# PCB.net
KiCad netlist of a schematic drawn in EasyEDA Pro
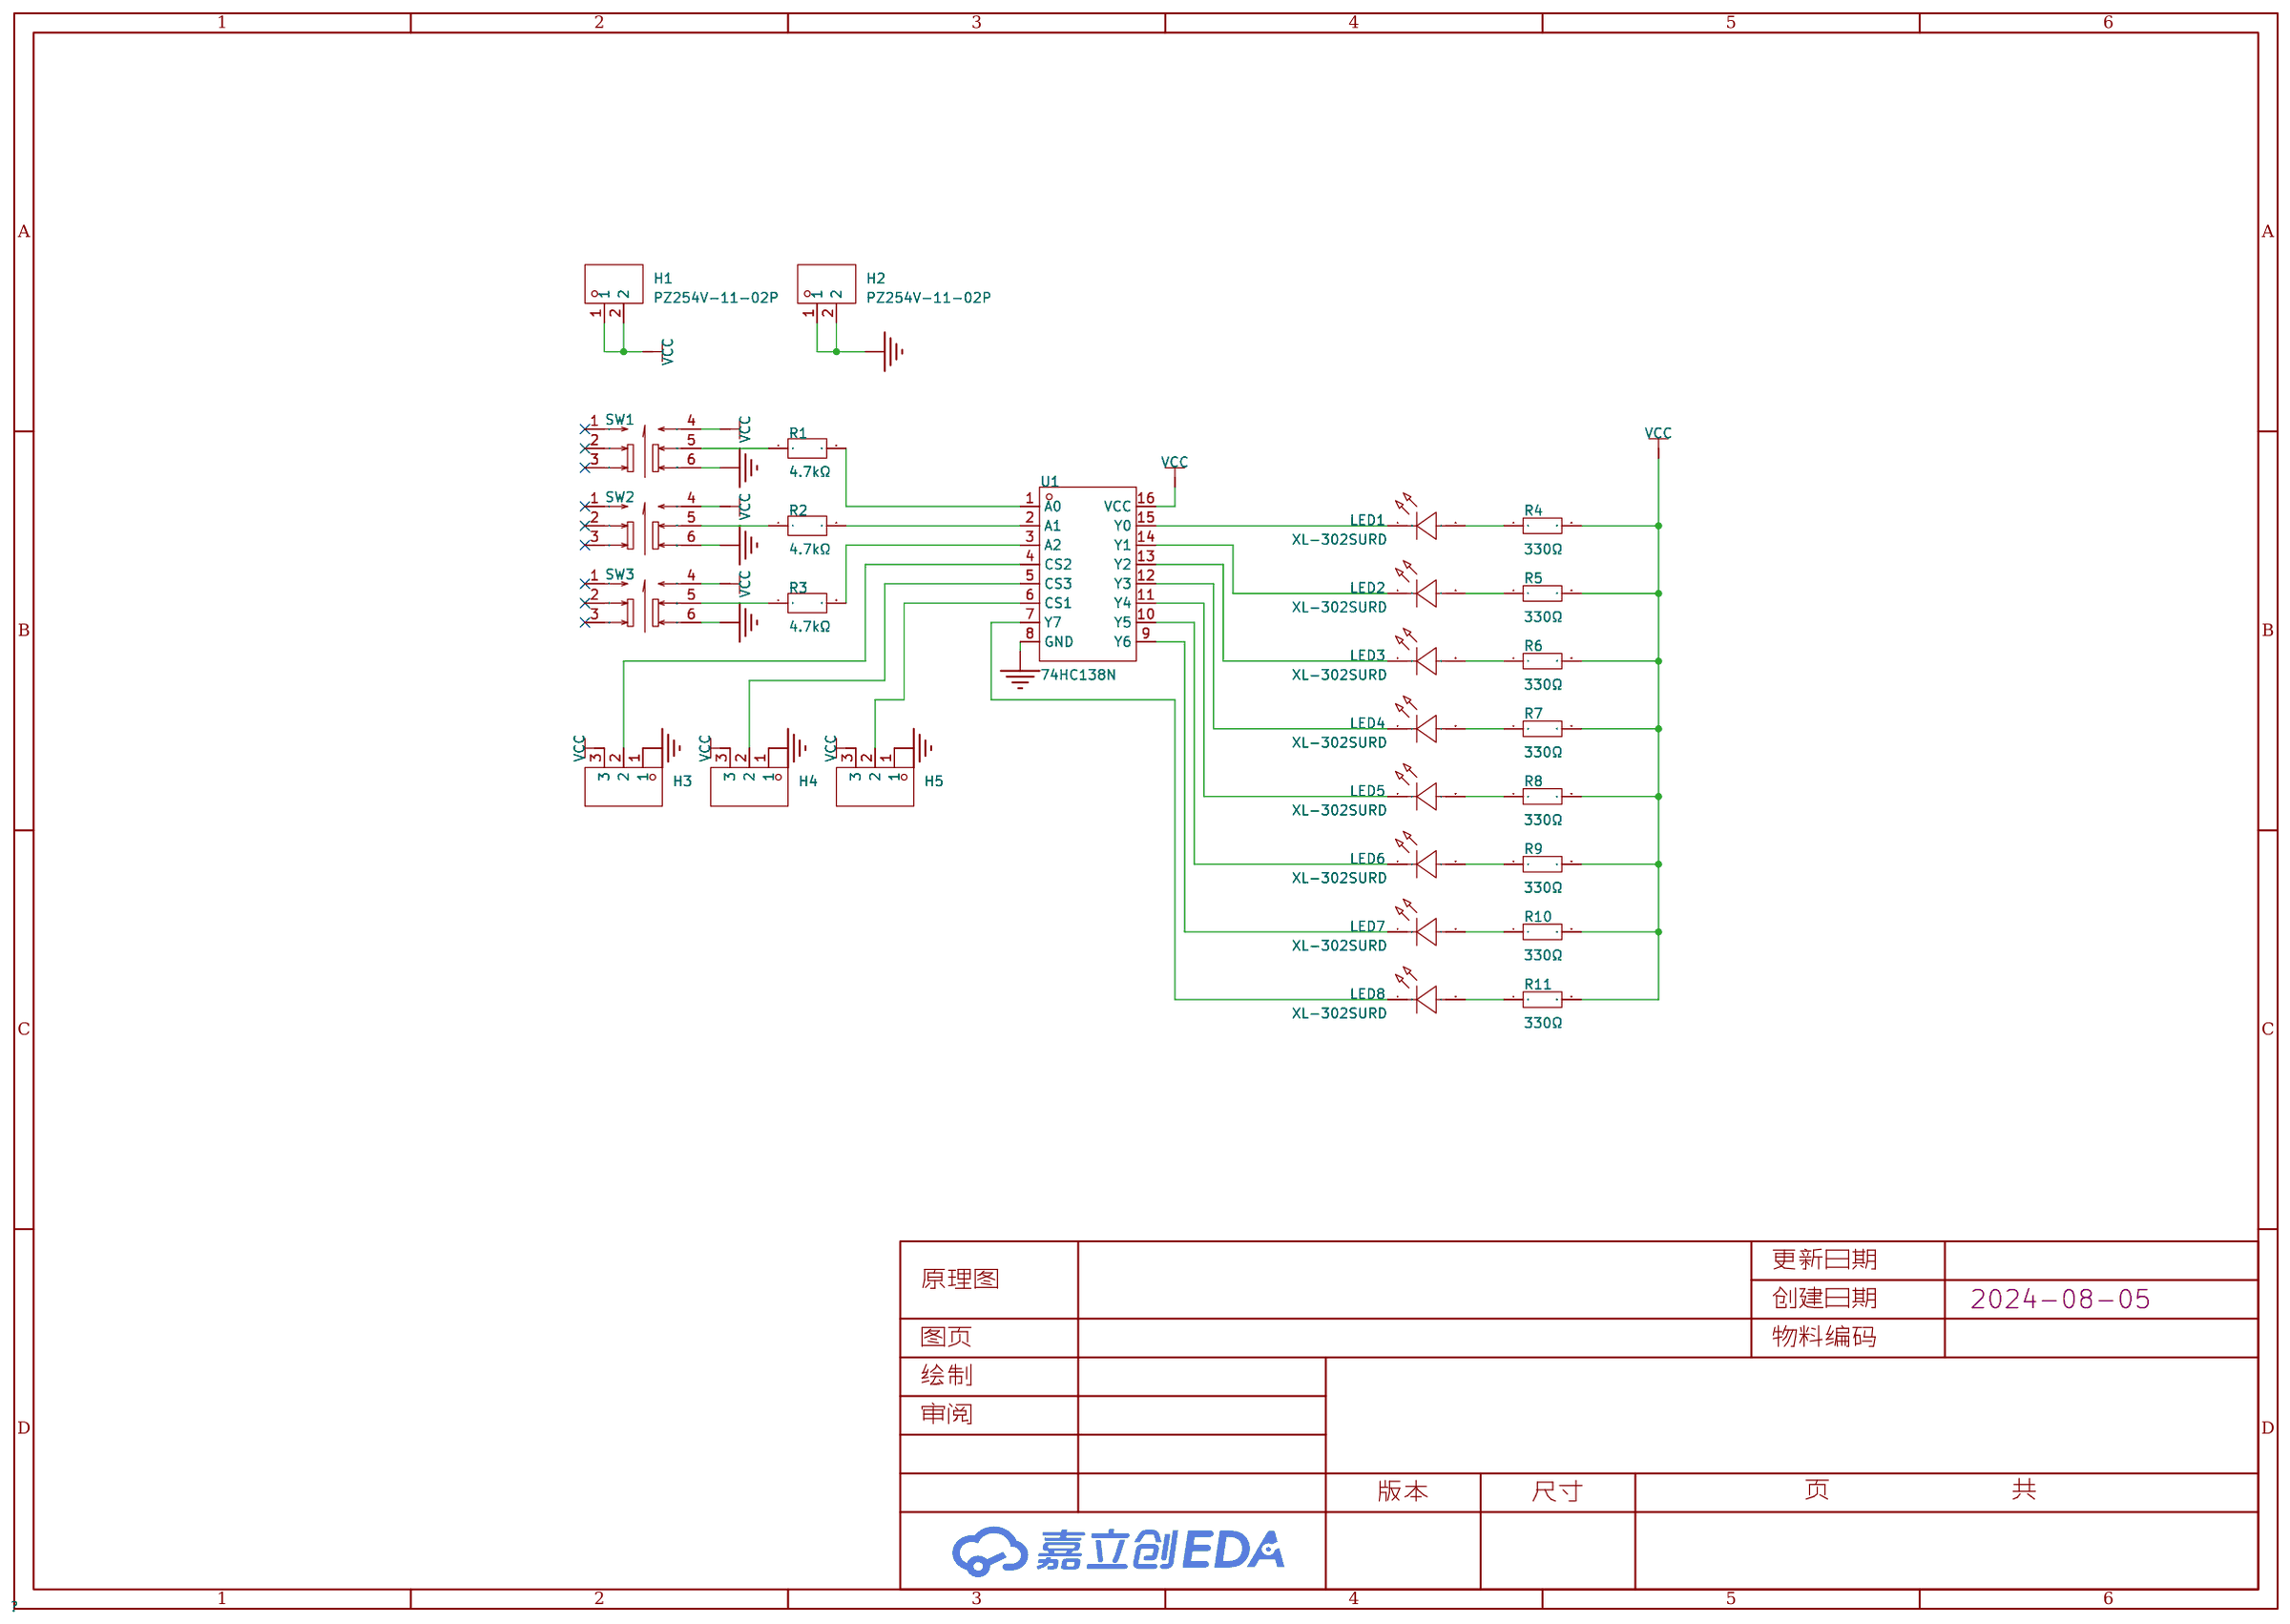
[diagram p0: 38译码电路]
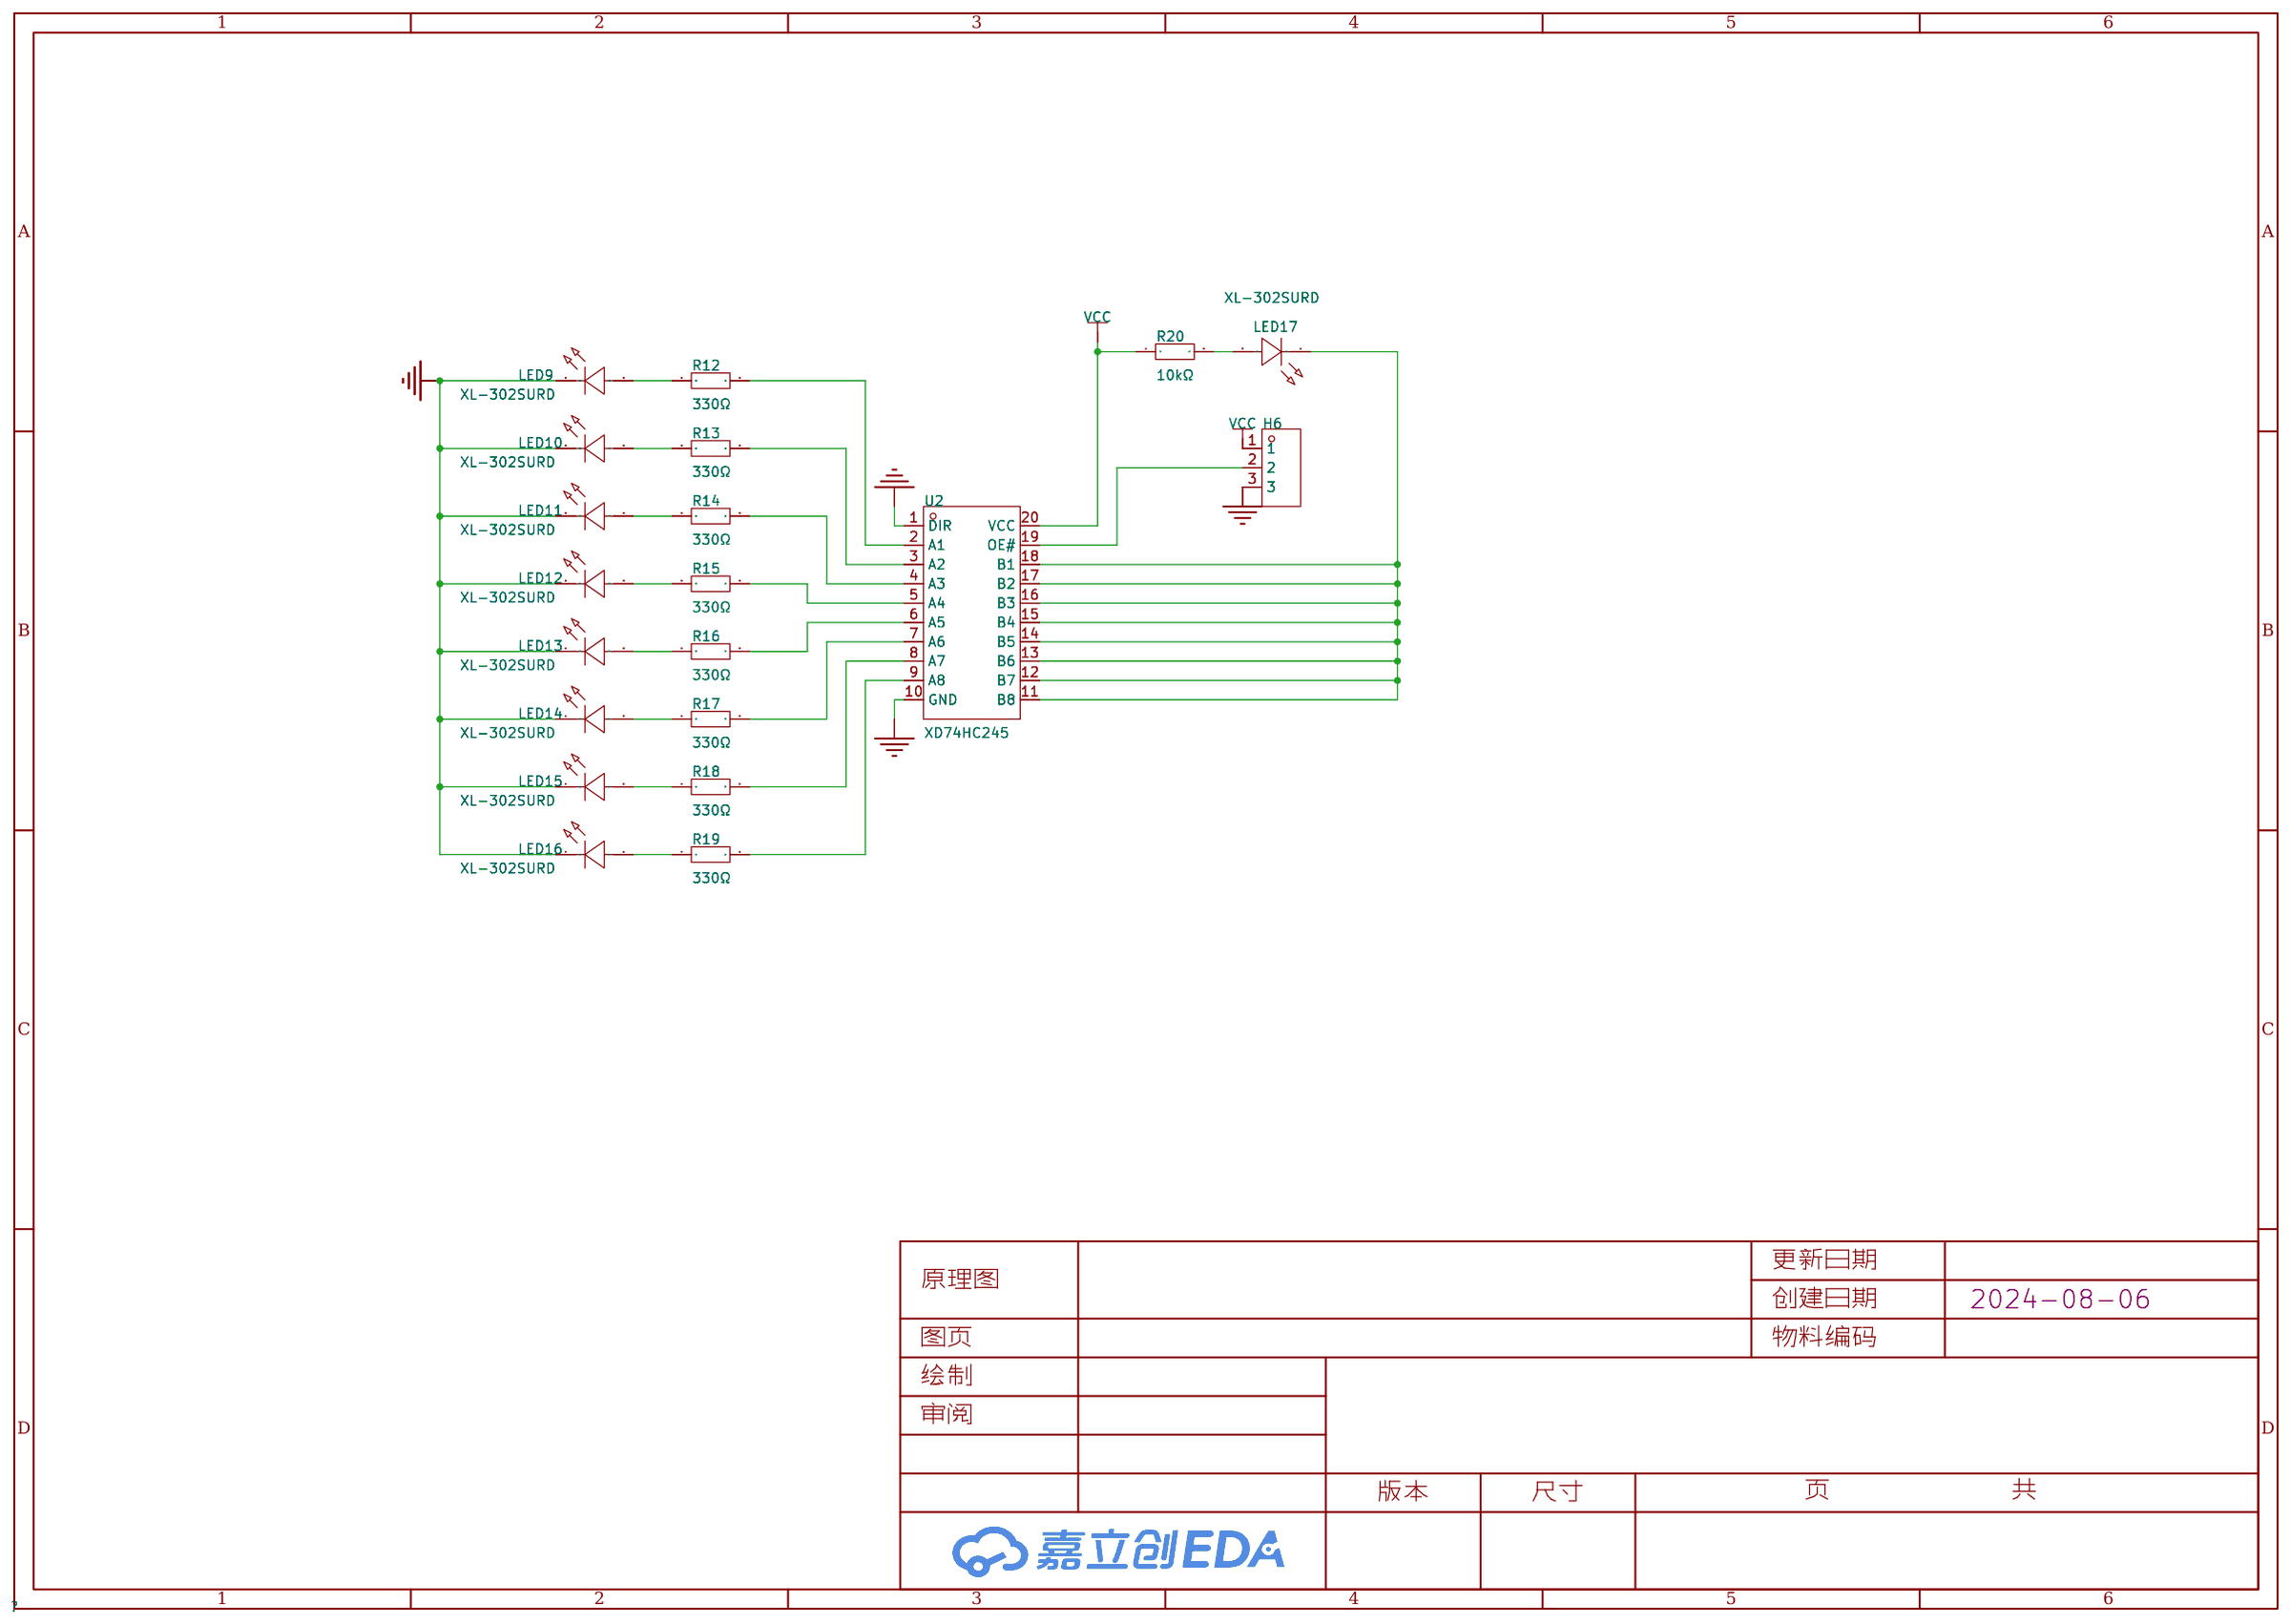
[diagram p1: 245信号放大电路]
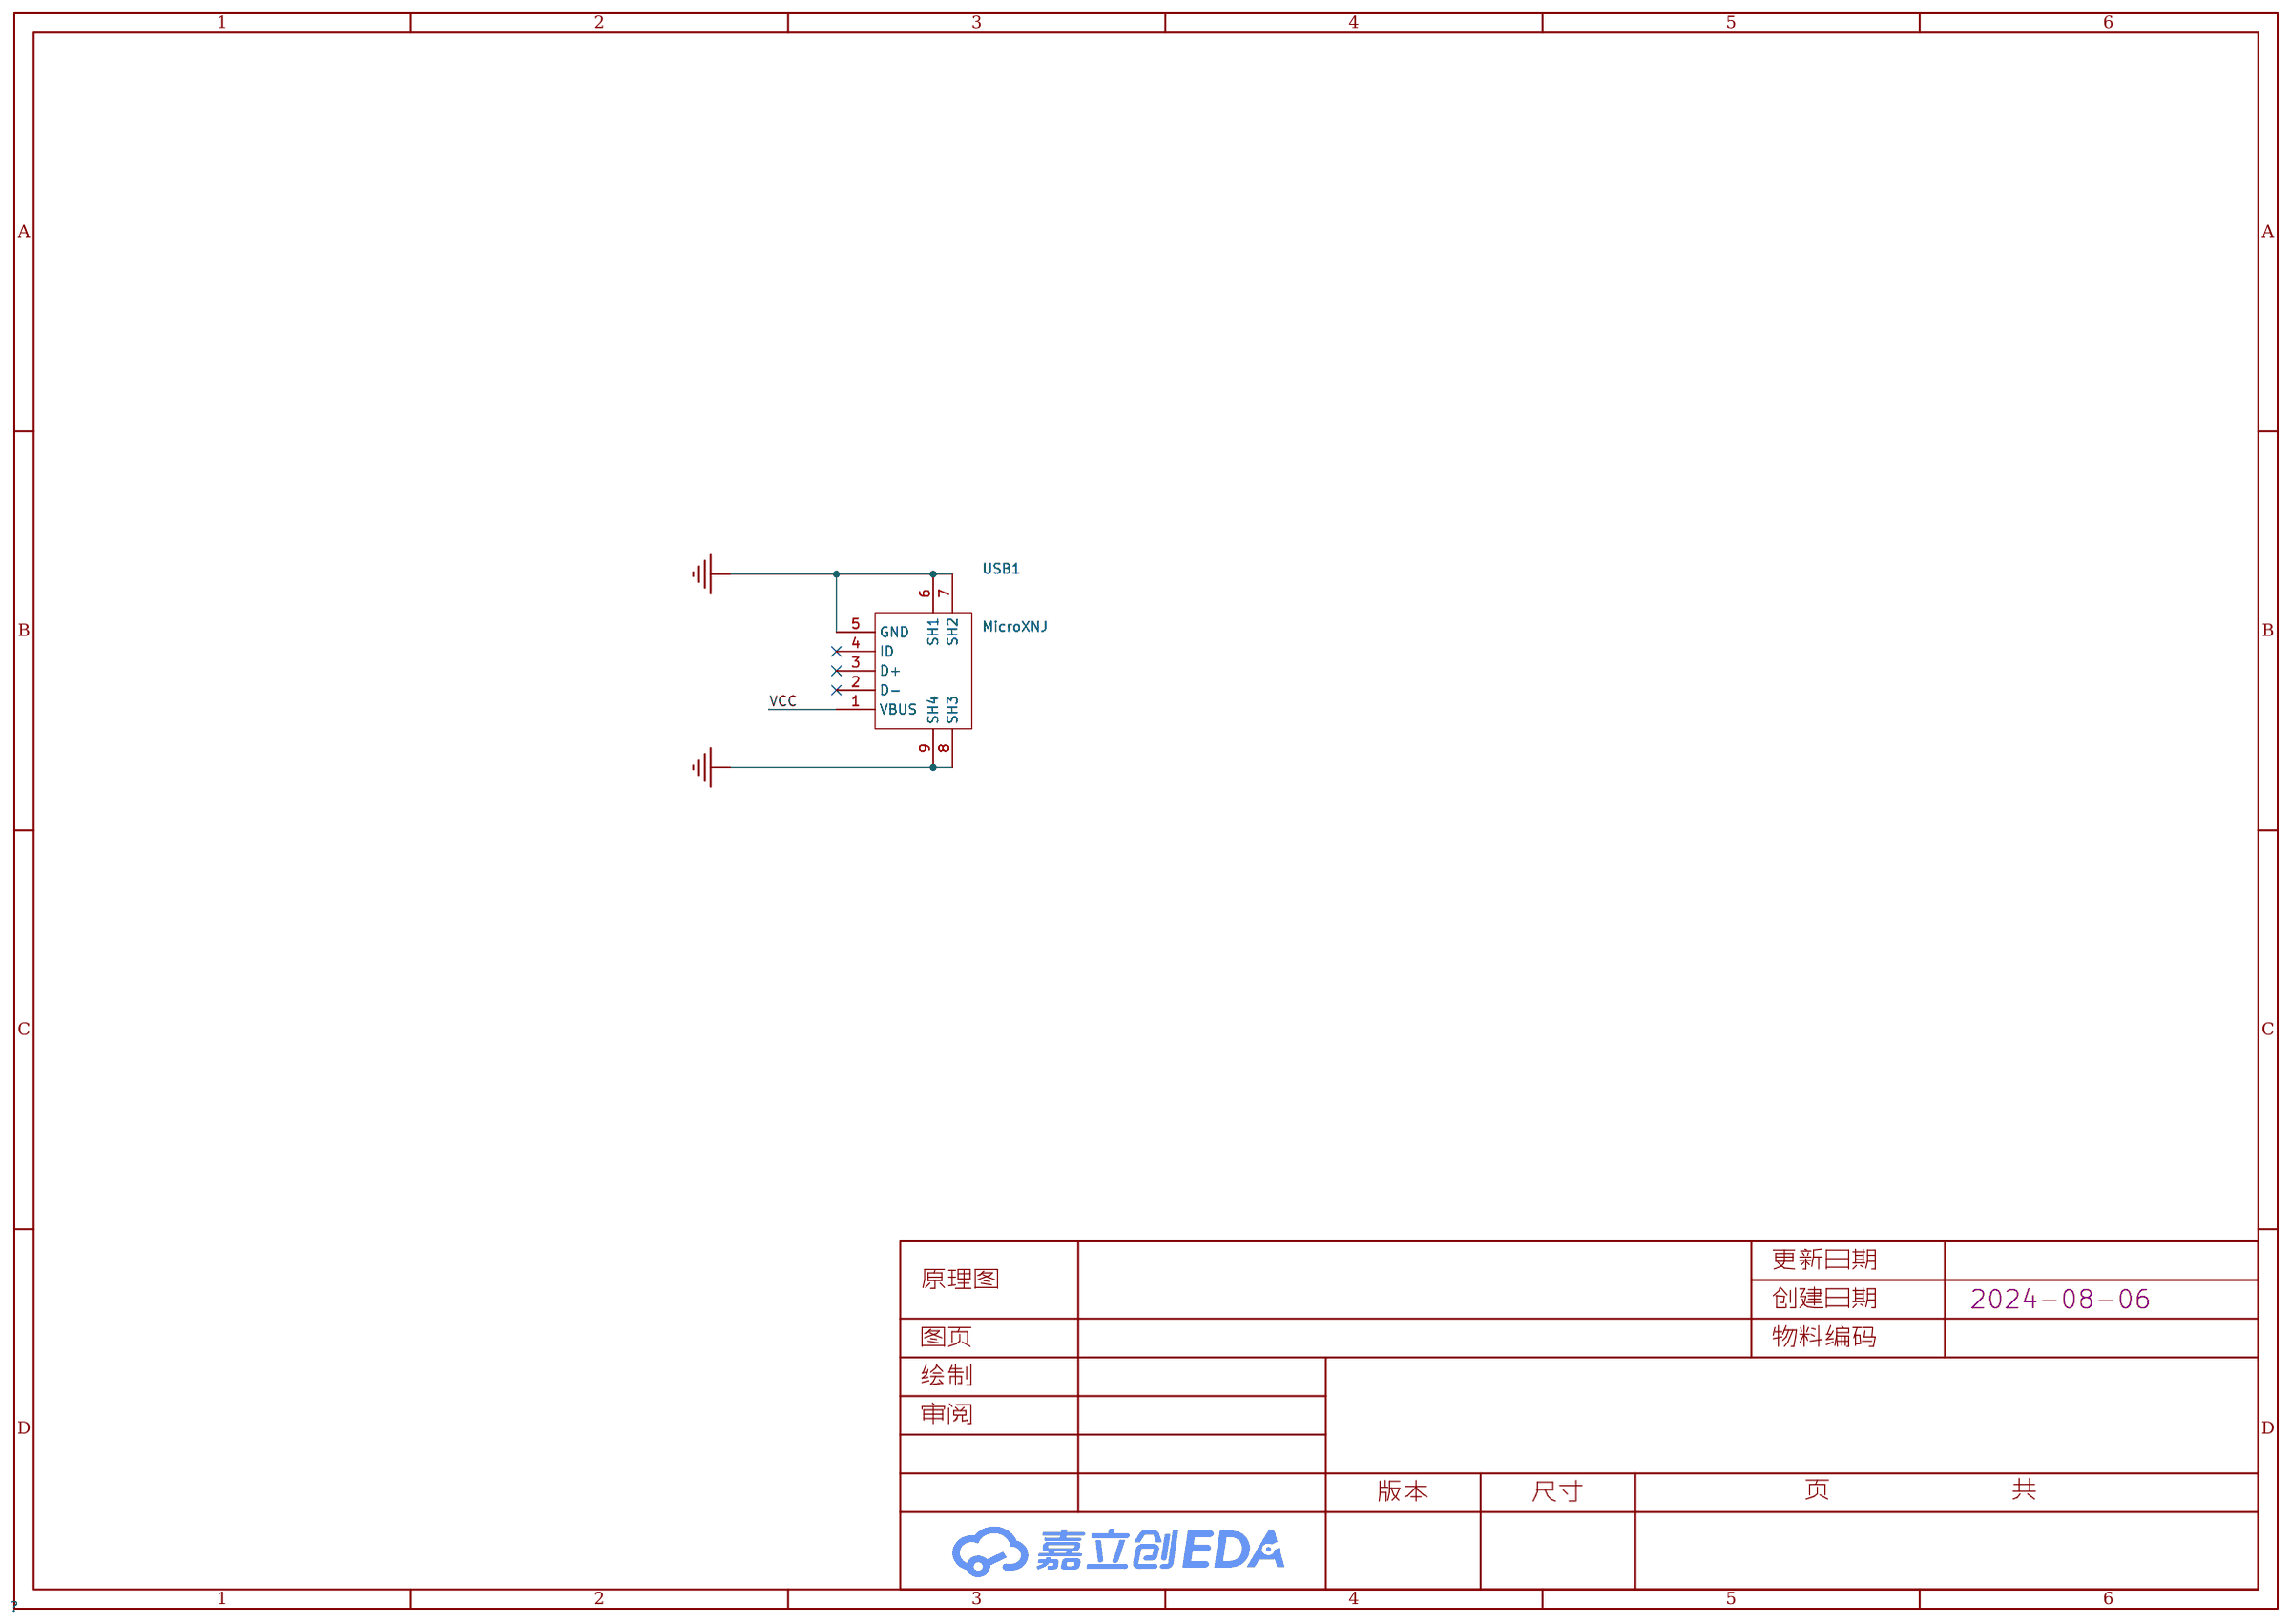
[diagram p2: usb供电]

(export (version "E")
  (design (tool "Eeschema 10.0.6"))
  (components
    (comp (ref "H1")
      (value "PZ254V-11-02P")
      (footprint "easyedapro:HDR-TH_2P-P2.54-V-M")
      (fields (field (name "Manufacturer") "XFCN(兴飞)"))
      (libsource (lib "easyedapro") (part "PZ254V-11-02P"))
    )
    (comp (ref "H2")
      (value "PZ254V-11-02P")
      (footprint "easyedapro:HDR-TH_2P-P2.54-V-M")
      (fields (field (name "Manufacturer") "XFCN(兴飞)"))
      (libsource (lib "easyedapro") (part "PZ254V-11-02P"))
    )
    (comp (ref "H3")
      (value "PZ254V-11-03P")
      (footprint "easyedapro:HDR-TH_3P-P2.54-V-M")
      (fields (field (name "Manufacturer") "XFCN(兴飞)"))
      (libsource (lib "easyedapro") (part "PZ254V-11-03P_C2937625"))
    )
    (comp (ref "H4")
      (value "PZ254V-11-03P")
      (footprint "easyedapro:HDR-TH_3P-P2.54-V-M")
      (fields (field (name "Manufacturer") "XFCN(兴飞)"))
      (libsource (lib "easyedapro") (part "PZ254V-11-03P_C2937625"))
    )
    (comp (ref "H5")
      (value "PZ254V-11-03P")
      (footprint "easyedapro:HDR-TH_3P-P2.54-V-M")
      (fields (field (name "Manufacturer") "XFCN(兴飞)"))
      (libsource (lib "easyedapro") (part "PZ254V-11-03P_C2937625"))
    )
    (comp (ref "LED1")
      (value "XL-302SURD")
      (footprint "easyedapro:LED-TH_BD3.8-P2.54-RD")
      (fields (field (name "Manufacturer") "XINGLIGHT(成兴光)"))
      (libsource (lib "easyedapro") (part "XL-302SURD"))
    )
    (comp (ref "LED2")
      (value "XL-302SURD")
      (footprint "easyedapro:LED-TH_BD3.8-P2.54-RD")
      (fields (field (name "Manufacturer") "XINGLIGHT(成兴光)"))
      (libsource (lib "easyedapro") (part "XL-302SURD"))
    )
    (comp (ref "LED3")
      (value "XL-302SURD")
      (footprint "easyedapro:LED-TH_BD3.8-P2.54-RD")
      (fields (field (name "Manufacturer") "XINGLIGHT(成兴光)"))
      (libsource (lib "easyedapro") (part "XL-302SURD"))
    )
    (comp (ref "LED4")
      (value "XL-302SURD")
      (footprint "easyedapro:LED-TH_BD3.8-P2.54-RD")
      (fields (field (name "Manufacturer") "XINGLIGHT(成兴光)"))
      (libsource (lib "easyedapro") (part "XL-302SURD"))
    )
    (comp (ref "LED5")
      (value "XL-302SURD")
      (footprint "easyedapro:LED-TH_BD3.8-P2.54-RD")
      (fields (field (name "Manufacturer") "XINGLIGHT(成兴光)"))
      (libsource (lib "easyedapro") (part "XL-302SURD"))
    )
    (comp (ref "LED6")
      (value "XL-302SURD")
      (footprint "easyedapro:LED-TH_BD3.8-P2.54-RD")
      (fields (field (name "Manufacturer") "XINGLIGHT(成兴光)"))
      (libsource (lib "easyedapro") (part "XL-302SURD"))
    )
    (comp (ref "LED7")
      (value "XL-302SURD")
      (footprint "easyedapro:LED-TH_BD3.8-P2.54-RD")
      (fields (field (name "Manufacturer") "XINGLIGHT(成兴光)"))
      (libsource (lib "easyedapro") (part "XL-302SURD"))
    )
    (comp (ref "LED8")
      (value "XL-302SURD")
      (footprint "easyedapro:LED-TH_BD3.8-P2.54-RD")
      (fields (field (name "Manufacturer") "XINGLIGHT(成兴光)"))
      (libsource (lib "easyedapro") (part "XL-302SURD"))
    )
    (comp (ref "R1")
      (value "4.7kΩ")
      (footprint "easyedapro:RES-TH_BD2.4-L6.3-P10.30-D0.6")
      (description "电阻类型:金属膜电阻;阻值:4.7kΩ;精度:±1%;功率:250mW;温度系数:±50ppm/°C;")
      (fields
        (field (name "Manufacturer Part") "RN1/4W4K7FT/BA1")
        (field (name "Manufacturer") "Tyohm(幸亚电阻)")
      )
      (libsource (lib "easyedapro") (part "RN 1/4W 4K7 F T/B A1"))
    )
    (comp (ref "R2")
      (value "4.7kΩ")
      (footprint "easyedapro:RES-TH_BD2.4-L6.3-P10.30-D0.6")
      (description "电阻类型:金属膜电阻;阻值:4.7kΩ;精度:±1%;功率:250mW;温度系数:±50ppm/°C;")
      (fields
        (field (name "Manufacturer Part") "RN1/4W4K7FT/BA1")
        (field (name "Manufacturer") "Tyohm(幸亚电阻)")
      )
      (libsource (lib "easyedapro") (part "RN 1/4W 4K7 F T/B A1"))
    )
    (comp (ref "R3")
      (value "4.7kΩ")
      (footprint "easyedapro:RES-TH_BD2.4-L6.3-P10.30-D0.6")
      (description "电阻类型:金属膜电阻;阻值:4.7kΩ;精度:±1%;功率:250mW;温度系数:±50ppm/°C;")
      (fields
        (field (name "Manufacturer Part") "RN1/4W4K7FT/BA1")
        (field (name "Manufacturer") "Tyohm(幸亚电阻)")
      )
      (libsource (lib "easyedapro") (part "RN 1/4W 4K7 F T/B A1"))
    )
    (comp (ref "R4")
      (value "330Ω")
      (footprint "easyedapro:RES-TH_BD2.3-L3.7-P7.70-D0.9")
      (description "电阻类型:金属膜电阻;阻值:330Ω;精度:±1%;功率:125mW;温度系数:±350ppm/°C;")
      (fields (field (name "Manufacturer Part") "MF1/8W-330Ω±1%-OT52") (field (name "Manufacturer") "VO(翔胜)"))
      (libsource (lib "easyedapro") (part "MF1/8W-330Ω±1%-OT52"))
    )
    (comp (ref "R5")
      (value "330Ω")
      (footprint "easyedapro:RES-TH_BD2.3-L3.7-P7.70-D0.9")
      (description "电阻类型:金属膜电阻;阻值:330Ω;精度:±1%;功率:125mW;温度系数:±350ppm/°C;")
      (fields (field (name "Manufacturer Part") "MF1/8W-330Ω±1%-OT52") (field (name "Manufacturer") "VO(翔胜)"))
      (libsource (lib "easyedapro") (part "MF1/8W-330Ω±1%-OT52"))
    )
    (comp (ref "R6")
      (value "330Ω")
      (footprint "easyedapro:RES-TH_BD2.3-L3.7-P7.70-D0.9")
      (description "电阻类型:金属膜电阻;阻值:330Ω;精度:±1%;功率:125mW;温度系数:±350ppm/°C;")
      (fields (field (name "Manufacturer Part") "MF1/8W-330Ω±1%-OT52") (field (name "Manufacturer") "VO(翔胜)"))
      (libsource (lib "easyedapro") (part "MF1/8W-330Ω±1%-OT52"))
    )
    (comp (ref "R7")
      (value "330Ω")
      (footprint "easyedapro:RES-TH_BD2.3-L3.7-P7.70-D0.9")
      (description "电阻类型:金属膜电阻;阻值:330Ω;精度:±1%;功率:125mW;温度系数:±350ppm/°C;")
      (fields (field (name "Manufacturer Part") "MF1/8W-330Ω±1%-OT52") (field (name "Manufacturer") "VO(翔胜)"))
      (libsource (lib "easyedapro") (part "MF1/8W-330Ω±1%-OT52"))
    )
    (comp (ref "R8")
      (value "330Ω")
      (footprint "easyedapro:RES-TH_BD2.3-L3.7-P7.70-D0.9")
      (description "电阻类型:金属膜电阻;阻值:330Ω;精度:±1%;功率:125mW;温度系数:±350ppm/°C;")
      (fields (field (name "Manufacturer Part") "MF1/8W-330Ω±1%-OT52") (field (name "Manufacturer") "VO(翔胜)"))
      (libsource (lib "easyedapro") (part "MF1/8W-330Ω±1%-OT52"))
    )
    (comp (ref "R9")
      (value "330Ω")
      (footprint "easyedapro:RES-TH_BD2.3-L3.7-P7.70-D0.9")
      (description "电阻类型:金属膜电阻;阻值:330Ω;精度:±1%;功率:125mW;温度系数:±350ppm/°C;")
      (fields (field (name "Manufacturer Part") "MF1/8W-330Ω±1%-OT52") (field (name "Manufacturer") "VO(翔胜)"))
      (libsource (lib "easyedapro") (part "MF1/8W-330Ω±1%-OT52"))
    )
    (comp (ref "R10")
      (value "330Ω")
      (footprint "easyedapro:RES-TH_BD2.3-L3.7-P7.70-D0.9")
      (description "电阻类型:金属膜电阻;阻值:330Ω;精度:±1%;功率:125mW;温度系数:±350ppm/°C;")
      (fields (field (name "Manufacturer Part") "MF1/8W-330Ω±1%-OT52") (field (name "Manufacturer") "VO(翔胜)"))
      (libsource (lib "easyedapro") (part "MF1/8W-330Ω±1%-OT52"))
    )
    (comp (ref "R11")
      (value "330Ω")
      (footprint "easyedapro:RES-TH_BD2.3-L3.7-P7.70-D0.9")
      (description "电阻类型:金属膜电阻;阻值:330Ω;精度:±1%;功率:125mW;温度系数:±350ppm/°C;")
      (fields (field (name "Manufacturer Part") "MF1/8W-330Ω±1%-OT52") (field (name "Manufacturer") "VO(翔胜)"))
      (libsource (lib "easyedapro") (part "MF1/8W-330Ω±1%-OT52"))
    )
    (comp (ref "SW1")
      (value "XKB7070-Z")
      (footprint "easyedapro:SW-TH_6P-L7.0-W7.0-P2.00")
      (description "自锁/无锁:自锁;安装方式:直插;触点电流:100mA;额定电压 (AC):250V;额定电压 (DC):30V;带灯:不带;作用力:160gf;机械寿命:10万次;")
      (fields (field (name "Manufacturer") "XKB Connectivity(中国星坤)"))
      (libsource (lib "easyedapro") (part "XKB7070-Z"))
    )
    (comp (ref "SW2")
      (value "XKB7070-Z")
      (footprint "easyedapro:SW-TH_6P-L7.0-W7.0-P2.00")
      (description "自锁/无锁:自锁;安装方式:直插;触点电流:100mA;额定电压 (AC):250V;额定电压 (DC):30V;带灯:不带;作用力:160gf;机械寿命:10万次;")
      (fields (field (name "Manufacturer") "XKB Connectivity(中国星坤)"))
      (libsource (lib "easyedapro") (part "XKB7070-Z"))
    )
    (comp (ref "SW3")
      (value "XKB7070-Z")
      (footprint "easyedapro:SW-TH_6P-L7.0-W7.0-P2.00")
      (description "自锁/无锁:自锁;安装方式:直插;触点电流:100mA;额定电压 (AC):250V;额定电压 (DC):30V;带灯:不带;作用力:160gf;机械寿命:10万次;")
      (fields (field (name "Manufacturer") "XKB Connectivity(中国星坤)"))
      (libsource (lib "easyedapro") (part "XKB7070-Z"))
    )
    (comp (ref "U1")
      (value "74HC138N")
      (footprint "easyedapro:DIP-16_L19.2-W6.6-P2.54-LS7.6-BL")
      (fields (field (name "Manufacturer") "HGSEMI(华冠)"))
      (libsource (lib "easyedapro") (part "74HC138N"))
    )
    (comp (ref "H6")
      (value "PZ254V-11-03P")
      (footprint "easyedapro:HDR-TH_3P-P2.54-V-M")
      (fields (field (name "Manufacturer") "XFCN(兴飞)"))
      (libsource (lib "easyedapro") (part "PZ254V-11-03P_C2937625"))
    )
    (comp (ref "LED9")
      (value "XL-302SURD")
      (footprint "easyedapro:LED-TH_BD3.8-P2.54-RD")
      (fields (field (name "Manufacturer") "XINGLIGHT(成兴光)"))
      (libsource (lib "easyedapro") (part "XL-302SURD"))
    )
    (comp (ref "LED10")
      (value "XL-302SURD")
      (footprint "easyedapro:LED-TH_BD3.8-P2.54-RD")
      (fields (field (name "Manufacturer") "XINGLIGHT(成兴光)"))
      (libsource (lib "easyedapro") (part "XL-302SURD"))
    )
    (comp (ref "LED11")
      (value "XL-302SURD")
      (footprint "easyedapro:LED-TH_BD3.8-P2.54-RD")
      (fields (field (name "Manufacturer") "XINGLIGHT(成兴光)"))
      (libsource (lib "easyedapro") (part "XL-302SURD"))
    )
    (comp (ref "LED12")
      (value "XL-302SURD")
      (footprint "easyedapro:LED-TH_BD3.8-P2.54-RD")
      (fields (field (name "Manufacturer") "XINGLIGHT(成兴光)"))
      (libsource (lib "easyedapro") (part "XL-302SURD"))
    )
    (comp (ref "LED13")
      (value "XL-302SURD")
      (footprint "easyedapro:LED-TH_BD3.8-P2.54-RD")
      (fields (field (name "Manufacturer") "XINGLIGHT(成兴光)"))
      (libsource (lib "easyedapro") (part "XL-302SURD"))
    )
    (comp (ref "LED14")
      (value "XL-302SURD")
      (footprint "easyedapro:LED-TH_BD3.8-P2.54-RD")
      (fields (field (name "Manufacturer") "XINGLIGHT(成兴光)"))
      (libsource (lib "easyedapro") (part "XL-302SURD"))
    )
    (comp (ref "LED15")
      (value "XL-302SURD")
      (footprint "easyedapro:LED-TH_BD3.8-P2.54-RD")
      (fields (field (name "Manufacturer") "XINGLIGHT(成兴光)"))
      (libsource (lib "easyedapro") (part "XL-302SURD"))
    )
    (comp (ref "LED16")
      (value "XL-302SURD")
      (footprint "easyedapro:LED-TH_BD3.8-P2.54-RD")
      (fields (field (name "Manufacturer") "XINGLIGHT(成兴光)"))
      (libsource (lib "easyedapro") (part "XL-302SURD"))
    )
    (comp (ref "LED17")
      (value "XL-302SURD")
      (footprint "easyedapro:LED-TH_BD3.8-P2.54-RD")
      (fields (field (name "Manufacturer") "XINGLIGHT(成兴光)"))
      (libsource (lib "easyedapro") (part "XL-302SURD"))
    )
    (comp (ref "R12")
      (value "330Ω")
      (footprint "easyedapro:RES-TH_BD2.3-L3.7-P7.70-D0.9")
      (description "电阻类型:金属膜电阻;阻值:330Ω;精度:±1%;功率:125mW;温度系数:±350ppm/°C;")
      (fields (field (name "Manufacturer Part") "MF1/8W-330Ω±1%-OT52") (field (name "Manufacturer") "VO(翔胜)"))
      (libsource (lib "easyedapro") (part "MF1/8W-330Ω±1%-OT52"))
    )
    (comp (ref "R13")
      (value "330Ω")
      (footprint "easyedapro:RES-TH_BD2.3-L3.7-P7.70-D0.9")
      (description "电阻类型:金属膜电阻;阻值:330Ω;精度:±1%;功率:125mW;温度系数:±350ppm/°C;")
      (fields (field (name "Manufacturer Part") "MF1/8W-330Ω±1%-OT52") (field (name "Manufacturer") "VO(翔胜)"))
      (libsource (lib "easyedapro") (part "MF1/8W-330Ω±1%-OT52"))
    )
    (comp (ref "R14")
      (value "330Ω")
      (footprint "easyedapro:RES-TH_BD2.3-L3.7-P7.70-D0.9")
      (description "电阻类型:金属膜电阻;阻值:330Ω;精度:±1%;功率:125mW;温度系数:±350ppm/°C;")
      (fields (field (name "Manufacturer Part") "MF1/8W-330Ω±1%-OT52") (field (name "Manufacturer") "VO(翔胜)"))
      (libsource (lib "easyedapro") (part "MF1/8W-330Ω±1%-OT52"))
    )
    (comp (ref "R15")
      (value "330Ω")
      (footprint "easyedapro:RES-TH_BD2.3-L3.7-P7.70-D0.9")
      (description "电阻类型:金属膜电阻;阻值:330Ω;精度:±1%;功率:125mW;温度系数:±350ppm/°C;")
      (fields (field (name "Manufacturer Part") "MF1/8W-330Ω±1%-OT52") (field (name "Manufacturer") "VO(翔胜)"))
      (libsource (lib "easyedapro") (part "MF1/8W-330Ω±1%-OT52"))
    )
    (comp (ref "R16")
      (value "330Ω")
      (footprint "easyedapro:RES-TH_BD2.3-L3.7-P7.70-D0.9")
      (description "电阻类型:金属膜电阻;阻值:330Ω;精度:±1%;功率:125mW;温度系数:±350ppm/°C;")
      (fields (field (name "Manufacturer Part") "MF1/8W-330Ω±1%-OT52") (field (name "Manufacturer") "VO(翔胜)"))
      (libsource (lib "easyedapro") (part "MF1/8W-330Ω±1%-OT52"))
    )
    (comp (ref "R17")
      (value "330Ω")
      (footprint "easyedapro:RES-TH_BD2.3-L3.7-P7.70-D0.9")
      (description "电阻类型:金属膜电阻;阻值:330Ω;精度:±1%;功率:125mW;温度系数:±350ppm/°C;")
      (fields (field (name "Manufacturer Part") "MF1/8W-330Ω±1%-OT52") (field (name "Manufacturer") "VO(翔胜)"))
      (libsource (lib "easyedapro") (part "MF1/8W-330Ω±1%-OT52"))
    )
    (comp (ref "R18")
      (value "330Ω")
      (footprint "easyedapro:RES-TH_BD2.3-L3.7-P7.70-D0.9")
      (description "电阻类型:金属膜电阻;阻值:330Ω;精度:±1%;功率:125mW;温度系数:±350ppm/°C;")
      (fields (field (name "Manufacturer Part") "MF1/8W-330Ω±1%-OT52") (field (name "Manufacturer") "VO(翔胜)"))
      (libsource (lib "easyedapro") (part "MF1/8W-330Ω±1%-OT52"))
    )
    (comp (ref "R19")
      (value "330Ω")
      (footprint "easyedapro:RES-TH_BD2.3-L3.7-P7.70-D0.9")
      (description "电阻类型:金属膜电阻;阻值:330Ω;精度:±1%;功率:125mW;温度系数:±350ppm/°C;")
      (fields (field (name "Manufacturer Part") "MF1/8W-330Ω±1%-OT52") (field (name "Manufacturer") "VO(翔胜)"))
      (libsource (lib "easyedapro") (part "MF1/8W-330Ω±1%-OT52"))
    )
    (comp (ref "R20")
      (value "10kΩ")
      (footprint "easyedapro:RES-TH_BD2.3-L6.5-P10.50-D0.5")
      (description "电阻类型:玻璃釉电阻;阻值:10kΩ;精度:±5%;功率:250mW;温度系数:±200ppm/°C;")
      (fields (field (name "Manufacturer Part") "RI40-1/4W-10KΩ±5%T") (field (name "Manufacturer") "华星机电"))
      (libsource (lib "easyedapro") (part "RI40-1/4W-10KΩ±5%T"))
    )
    (comp (ref "U2")
      (value "XD74HC245")
      (footprint "easyedapro:DIP-20_L26.8-W6.4-P2.54-LS7.6-BL")
      (fields (field (name "Manufacturer") "XINLUDA(信路达)"))
      (libsource (lib "easyedapro") (part "XD74HC245"))
    )
    (comp (ref "USB1")
      (value "MicroXNJ")
      (footprint "easyedapro:MICRO-USB-SMD_MICROXNJ")
      (description "连接器类型:Micro-B;标准:USB 2.0;公母:母;安装方式:卧贴;触点数量:5P;端口数量:1;额定电流 - 电源:1A;工作温度范围:-20°C~+85°C;")
      (fields (field (name "Manufacturer") "SHOU HAN(首韩)"))
      (libsource (lib "easyedapro") (part "MICROXNJ"))
    )
  )
  (nets
    (net (code "1") (name "GND") (class "Default")
      (node (ref "H2") (pin "1") (pinfunction "1_1") (pintype "unspecified"))
      (node (ref "H2") (pin "2") (pinfunction "2_2") (pintype "unspecified"))
      (node (ref "H3") (pin "1") (pinfunction "1_1") (pintype "unspecified"))
      (node (ref "H4") (pin "1") (pinfunction "1_1") (pintype "unspecified"))
      (node (ref "H5") (pin "1") (pinfunction "1_1") (pintype "unspecified"))
      (node (ref "H6") (pin "3") (pinfunction "3_3") (pintype "unspecified"))
      (node (ref "LED10") (pin "1") (pinfunction "K_1") (pintype "unspecified"))
      (node (ref "LED11") (pin "1") (pinfunction "K_1") (pintype "unspecified"))
      (node (ref "LED12") (pin "1") (pinfunction "K_1") (pintype "unspecified"))
      (node (ref "LED13") (pin "1") (pinfunction "K_1") (pintype "unspecified"))
      (node (ref "LED14") (pin "1") (pinfunction "K_1") (pintype "unspecified"))
      (node (ref "LED15") (pin "1") (pinfunction "K_1") (pintype "unspecified"))
      (node (ref "LED16") (pin "1") (pinfunction "K_1") (pintype "unspecified"))
      (node (ref "LED9") (pin "1") (pinfunction "K_1") (pintype "unspecified"))
      (node (ref "SW1") (pin "6") (pinfunction "6_6") (pintype "unspecified"))
      (node (ref "SW2") (pin "6") (pinfunction "6_6") (pintype "unspecified"))
      (node (ref "SW3") (pin "6") (pinfunction "6_6") (pintype "unspecified"))
      (node (ref "U1") (pin "8") (pinfunction "GND_8") (pintype "input"))
      (node (ref "U2") (pin "1") (pinfunction "DIR_1") (pintype "unspecified"))
      (node (ref "U2") (pin "10") (pinfunction "GND_10") (pintype "unspecified"))
      (node (ref "USB1") (pin "5") (pinfunction "GND_5") (pintype "unspecified"))
      (node (ref "USB1") (pin "6") (pinfunction "SH1_6") (pintype "unspecified"))
      (node (ref "USB1") (pin "7") (pinfunction "SH2_7") (pintype "unspecified"))
      (node (ref "USB1") (pin "8") (pinfunction "SH3_8") (pintype "unspecified"))
      (node (ref "USB1") (pin "9") (pinfunction "SH4_9") (pintype "unspecified"))
    )
    (net (code "2") (name "Net-(LED1-A)") (class "Default")
      (node (ref "LED1") (pin "2") (pinfunction "A_2") (pintype "unspecified"))
      (node (ref "R4") (pin "1") (pinfunction "1_1") (pintype "unspecified"))
    )
    (net (code "3") (name "Net-(LED1-K)") (class "Default")
      (node (ref "LED1") (pin "1") (pinfunction "K_1") (pintype "unspecified"))
      (node (ref "U1") (pin "15") (pinfunction "Y0_15") (pintype "input"))
    )
    (net (code "4") (name "Net-(LED2-A)") (class "Default")
      (node (ref "LED2") (pin "2") (pinfunction "A_2") (pintype "unspecified"))
      (node (ref "R5") (pin "1") (pinfunction "1_1") (pintype "unspecified"))
    )
    (net (code "5") (name "Net-(LED2-K)") (class "Default")
      (node (ref "LED2") (pin "1") (pinfunction "K_1") (pintype "unspecified"))
      (node (ref "U1") (pin "14") (pinfunction "Y1_14") (pintype "input"))
    )
    (net (code "6") (name "Net-(LED3-A)") (class "Default")
      (node (ref "LED3") (pin "2") (pinfunction "A_2") (pintype "unspecified"))
      (node (ref "R6") (pin "1") (pinfunction "1_1") (pintype "unspecified"))
    )
    (net (code "7") (name "Net-(LED3-K)") (class "Default")
      (node (ref "LED3") (pin "1") (pinfunction "K_1") (pintype "unspecified"))
      (node (ref "U1") (pin "13") (pinfunction "Y2_13") (pintype "input"))
    )
    (net (code "8") (name "Net-(LED4-A)") (class "Default")
      (node (ref "LED4") (pin "2") (pinfunction "A_2") (pintype "unspecified"))
      (node (ref "R7") (pin "1") (pinfunction "1_1") (pintype "unspecified"))
    )
    (net (code "9") (name "Net-(LED4-K)") (class "Default")
      (node (ref "LED4") (pin "1") (pinfunction "K_1") (pintype "unspecified"))
      (node (ref "U1") (pin "12") (pinfunction "Y3_12") (pintype "input"))
    )
    (net (code "10") (name "Net-(LED5-A)") (class "Default")
      (node (ref "LED5") (pin "2") (pinfunction "A_2") (pintype "unspecified"))
      (node (ref "R8") (pin "1") (pinfunction "1_1") (pintype "unspecified"))
    )
    (net (code "11") (name "Net-(LED5-K)") (class "Default")
      (node (ref "LED5") (pin "1") (pinfunction "K_1") (pintype "unspecified"))
      (node (ref "U1") (pin "11") (pinfunction "Y4_11") (pintype "input"))
    )
    (net (code "12") (name "Net-(LED6-A)") (class "Default")
      (node (ref "LED6") (pin "2") (pinfunction "A_2") (pintype "unspecified"))
      (node (ref "R9") (pin "1") (pinfunction "1_1") (pintype "unspecified"))
    )
    (net (code "13") (name "Net-(LED6-K)") (class "Default")
      (node (ref "LED6") (pin "1") (pinfunction "K_1") (pintype "unspecified"))
      (node (ref "U1") (pin "10") (pinfunction "Y5_10") (pintype "input"))
    )
    (net (code "14") (name "Net-(LED7-A)") (class "Default")
      (node (ref "LED7") (pin "2") (pinfunction "A_2") (pintype "unspecified"))
      (node (ref "R10") (pin "1") (pinfunction "1_1") (pintype "unspecified"))
    )
    (net (code "15") (name "Net-(LED7-K)") (class "Default")
      (node (ref "LED7") (pin "1") (pinfunction "K_1") (pintype "unspecified"))
      (node (ref "U1") (pin "9") (pinfunction "Y6_9") (pintype "input"))
    )
    (net (code "16") (name "Net-(LED8-A)") (class "Default")
      (node (ref "LED8") (pin "2") (pinfunction "A_2") (pintype "unspecified"))
      (node (ref "R11") (pin "1") (pinfunction "1_1") (pintype "unspecified"))
    )
    (net (code "17") (name "Net-(LED8-K)") (class "Default")
      (node (ref "LED8") (pin "1") (pinfunction "K_1") (pintype "unspecified"))
      (node (ref "U1") (pin "7") (pinfunction "Y7_7") (pintype "input"))
    )
    (net (code "18") (name "Net-(LED9-A)") (class "Default")
      (node (ref "LED9") (pin "2") (pinfunction "A_2") (pintype "unspecified"))
      (node (ref "R12") (pin "1") (pinfunction "1_1") (pintype "unspecified"))
    )
    (net (code "19") (name "Net-(LED10-A)") (class "Default")
      (node (ref "LED10") (pin "2") (pinfunction "A_2") (pintype "unspecified"))
      (node (ref "R13") (pin "1") (pinfunction "1_1") (pintype "unspecified"))
    )
    (net (code "20") (name "Net-(LED11-A)") (class "Default")
      (node (ref "LED11") (pin "2") (pinfunction "A_2") (pintype "unspecified"))
      (node (ref "R14") (pin "1") (pinfunction "1_1") (pintype "unspecified"))
    )
    (net (code "21") (name "Net-(LED12-A)") (class "Default")
      (node (ref "LED12") (pin "2") (pinfunction "A_2") (pintype "unspecified"))
      (node (ref "R15") (pin "1") (pinfunction "1_1") (pintype "unspecified"))
    )
    (net (code "22") (name "Net-(LED13-A)") (class "Default")
      (node (ref "LED13") (pin "2") (pinfunction "A_2") (pintype "unspecified"))
      (node (ref "R16") (pin "1") (pinfunction "1_1") (pintype "unspecified"))
    )
    (net (code "23") (name "Net-(LED14-A)") (class "Default")
      (node (ref "LED14") (pin "2") (pinfunction "A_2") (pintype "unspecified"))
      (node (ref "R17") (pin "1") (pinfunction "1_1") (pintype "unspecified"))
    )
    (net (code "24") (name "Net-(LED15-A)") (class "Default")
      (node (ref "LED15") (pin "2") (pinfunction "A_2") (pintype "unspecified"))
      (node (ref "R18") (pin "1") (pinfunction "1_1") (pintype "unspecified"))
    )
    (net (code "25") (name "Net-(LED16-A)") (class "Default")
      (node (ref "LED16") (pin "2") (pinfunction "A_2") (pintype "unspecified"))
      (node (ref "R19") (pin "1") (pinfunction "1_1") (pintype "unspecified"))
    )
    (net (code "26") (name "Net-(LED17-A)") (class "Default")
      (node (ref "LED17") (pin "2") (pinfunction "A_2") (pintype "unspecified"))
      (node (ref "R20") (pin "2") (pinfunction "2_2") (pintype "unspecified"))
    )
    (net (code "27") (name "Net-(LED17-K)") (class "Default")
      (node (ref "LED17") (pin "1") (pinfunction "K_1") (pintype "unspecified"))
      (node (ref "U2") (pin "11") (pinfunction "B8_11") (pintype "unspecified"))
      (node (ref "U2") (pin "12") (pinfunction "B7_12") (pintype "unspecified"))
      (node (ref "U2") (pin "13") (pinfunction "B6_13") (pintype "unspecified"))
      (node (ref "U2") (pin "14") (pinfunction "B5_14") (pintype "unspecified"))
      (node (ref "U2") (pin "15") (pinfunction "B4_15") (pintype "unspecified"))
      (node (ref "U2") (pin "16") (pinfunction "B3_16") (pintype "unspecified"))
      (node (ref "U2") (pin "17") (pinfunction "B2_17") (pintype "unspecified"))
      (node (ref "U2") (pin "18") (pinfunction "B1_18") (pintype "unspecified"))
    )
    (net (code "28") (name "Net-(R1-Pad1)") (class "Default")
      (node (ref "R1") (pin "1") (pinfunction "1_1") (pintype "unspecified"))
      (node (ref "SW1") (pin "5") (pinfunction "5_5") (pintype "unspecified"))
    )
    (net (code "29") (name "Net-(R2-Pad1)") (class "Default")
      (node (ref "R2") (pin "1") (pinfunction "1_1") (pintype "unspecified"))
      (node (ref "SW2") (pin "5") (pinfunction "5_5") (pintype "unspecified"))
    )
    (net (code "30") (name "Net-(R3-Pad1)") (class "Default")
      (node (ref "R3") (pin "1") (pinfunction "1_1") (pintype "unspecified"))
      (node (ref "SW3") (pin "5") (pinfunction "5_5") (pintype "unspecified"))
    )
    (net (code "31") (name "Net-(U1-A0)") (class "Default")
      (node (ref "R1") (pin "2") (pinfunction "2_2") (pintype "unspecified"))
      (node (ref "U1") (pin "1") (pinfunction "A0_1") (pintype "input"))
    )
    (net (code "32") (name "Net-(U1-A1)") (class "Default")
      (node (ref "R2") (pin "2") (pinfunction "2_2") (pintype "unspecified"))
      (node (ref "U1") (pin "2") (pinfunction "A1_2") (pintype "input"))
    )
    (net (code "33") (name "Net-(U1-A2)") (class "Default")
      (node (ref "R3") (pin "2") (pinfunction "2_2") (pintype "unspecified"))
      (node (ref "U1") (pin "3") (pinfunction "A2_3") (pintype "input"))
    )
    (net (code "34") (name "Net-(U1-CS1)") (class "Default")
      (node (ref "H5") (pin "2") (pinfunction "2_2") (pintype "unspecified"))
      (node (ref "U1") (pin "6") (pinfunction "CS1_6") (pintype "input"))
    )
    (net (code "35") (name "Net-(U1-CS2)") (class "Default")
      (node (ref "H3") (pin "2") (pinfunction "2_2") (pintype "unspecified"))
      (node (ref "U1") (pin "4") (pinfunction "CS2_4") (pintype "input"))
    )
    (net (code "36") (name "Net-(U1-CS3)") (class "Default")
      (node (ref "H4") (pin "2") (pinfunction "2_2") (pintype "unspecified"))
      (node (ref "U1") (pin "5") (pinfunction "CS3_5") (pintype "input"))
    )
    (net (code "37") (name "Net-(U2-A1)") (class "Default")
      (node (ref "R12") (pin "2") (pinfunction "2_2") (pintype "unspecified"))
      (node (ref "U2") (pin "2") (pinfunction "A1_2") (pintype "unspecified"))
    )
    (net (code "38") (name "Net-(U2-A2)") (class "Default")
      (node (ref "R13") (pin "2") (pinfunction "2_2") (pintype "unspecified"))
      (node (ref "U2") (pin "3") (pinfunction "A2_3") (pintype "unspecified"))
    )
    (net (code "39") (name "Net-(U2-A3)") (class "Default")
      (node (ref "R14") (pin "2") (pinfunction "2_2") (pintype "unspecified"))
      (node (ref "U2") (pin "4") (pinfunction "A3_4") (pintype "unspecified"))
    )
    (net (code "40") (name "Net-(U2-A4)") (class "Default")
      (node (ref "R15") (pin "2") (pinfunction "2_2") (pintype "unspecified"))
      (node (ref "U2") (pin "5") (pinfunction "A4_5") (pintype "unspecified"))
    )
    (net (code "41") (name "Net-(U2-A5)") (class "Default")
      (node (ref "R16") (pin "2") (pinfunction "2_2") (pintype "unspecified"))
      (node (ref "U2") (pin "6") (pinfunction "A5_6") (pintype "unspecified"))
    )
    (net (code "42") (name "Net-(U2-A6)") (class "Default")
      (node (ref "R17") (pin "2") (pinfunction "2_2") (pintype "unspecified"))
      (node (ref "U2") (pin "7") (pinfunction "A6_7") (pintype "unspecified"))
    )
    (net (code "43") (name "Net-(U2-A7)") (class "Default")
      (node (ref "R18") (pin "2") (pinfunction "2_2") (pintype "unspecified"))
      (node (ref "U2") (pin "8") (pinfunction "A7_8") (pintype "unspecified"))
    )
    (net (code "44") (name "Net-(U2-A8)") (class "Default")
      (node (ref "R19") (pin "2") (pinfunction "2_2") (pintype "unspecified"))
      (node (ref "U2") (pin "9") (pinfunction "A8_9") (pintype "unspecified"))
    )
    (net (code "45") (name "Net-(U2-OE#)") (class "Default")
      (node (ref "H6") (pin "2") (pinfunction "2_2") (pintype "unspecified"))
      (node (ref "U2") (pin "19") (pinfunction "OE#_19") (pintype "unspecified"))
    )
    (net (code "46") (name "VCC") (class "Default")
      (node (ref "H1") (pin "1") (pinfunction "1_1") (pintype "unspecified"))
      (node (ref "H1") (pin "2") (pinfunction "2_2") (pintype "unspecified"))
      (node (ref "H3") (pin "3") (pinfunction "3_3") (pintype "unspecified"))
      (node (ref "H4") (pin "3") (pinfunction "3_3") (pintype "unspecified"))
      (node (ref "H5") (pin "3") (pinfunction "3_3") (pintype "unspecified"))
      (node (ref "H6") (pin "1") (pinfunction "1_1") (pintype "unspecified"))
      (node (ref "R10") (pin "2") (pinfunction "2_2") (pintype "unspecified"))
      (node (ref "R11") (pin "2") (pinfunction "2_2") (pintype "unspecified"))
      (node (ref "R20") (pin "1") (pinfunction "1_1") (pintype "unspecified"))
      (node (ref "R4") (pin "2") (pinfunction "2_2") (pintype "unspecified"))
      (node (ref "R5") (pin "2") (pinfunction "2_2") (pintype "unspecified"))
      (node (ref "R6") (pin "2") (pinfunction "2_2") (pintype "unspecified"))
      (node (ref "R7") (pin "2") (pinfunction "2_2") (pintype "unspecified"))
      (node (ref "R8") (pin "2") (pinfunction "2_2") (pintype "unspecified"))
      (node (ref "R9") (pin "2") (pinfunction "2_2") (pintype "unspecified"))
      (node (ref "SW1") (pin "4") (pinfunction "4_4") (pintype "unspecified"))
      (node (ref "SW2") (pin "4") (pinfunction "4_4") (pintype "unspecified"))
      (node (ref "SW3") (pin "4") (pinfunction "4_4") (pintype "unspecified"))
      (node (ref "U1") (pin "16") (pinfunction "VCC_16") (pintype "input"))
      (node (ref "U2") (pin "20") (pinfunction "VCC_20") (pintype "unspecified"))
      (node (ref "USB1") (pin "1") (pinfunction "VBUS_1") (pintype "unspecified"))
    )
    (net (code "47") (name "unconnected-(SW1-Pad1)") (class "Default")
      (node (ref "SW1") (pin "1") (pinfunction "1_1") (pintype "unspecified+no_connect"))
    )
    (net (code "48") (name "unconnected-(SW1-Pad2)") (class "Default")
      (node (ref "SW1") (pin "2") (pinfunction "2_2") (pintype "unspecified+no_connect"))
    )
    (net (code "49") (name "unconnected-(SW1-Pad3)") (class "Default")
      (node (ref "SW1") (pin "3") (pinfunction "3_3") (pintype "unspecified+no_connect"))
    )
    (net (code "50") (name "unconnected-(SW2-Pad1)") (class "Default")
      (node (ref "SW2") (pin "1") (pinfunction "1_1") (pintype "unspecified+no_connect"))
    )
    (net (code "51") (name "unconnected-(SW2-Pad2)") (class "Default")
      (node (ref "SW2") (pin "2") (pinfunction "2_2") (pintype "unspecified+no_connect"))
    )
    (net (code "52") (name "unconnected-(SW2-Pad3)") (class "Default")
      (node (ref "SW2") (pin "3") (pinfunction "3_3") (pintype "unspecified+no_connect"))
    )
    (net (code "53") (name "unconnected-(SW3-Pad1)") (class "Default")
      (node (ref "SW3") (pin "1") (pinfunction "1_1") (pintype "unspecified+no_connect"))
    )
    (net (code "54") (name "unconnected-(SW3-Pad2)") (class "Default")
      (node (ref "SW3") (pin "2") (pinfunction "2_2") (pintype "unspecified+no_connect"))
    )
    (net (code "55") (name "unconnected-(SW3-Pad3)") (class "Default")
      (node (ref "SW3") (pin "3") (pinfunction "3_3") (pintype "unspecified+no_connect"))
    )
    (net (code "56") (name "unconnected-(USB1-D+-Pad3)") (class "Default")
      (node (ref "USB1") (pin "3") (pinfunction "D+_3") (pintype "unspecified+no_connect"))
    )
    (net (code "57") (name "unconnected-(USB1-D--Pad2)") (class "Default")
      (node (ref "USB1") (pin "2") (pinfunction "D-_2") (pintype "unspecified+no_connect"))
    )
    (net (code "58") (name "unconnected-(USB1-ID-Pad4)") (class "Default")
      (node (ref "USB1") (pin "4") (pinfunction "ID_4") (pintype "unspecified+no_connect"))
    )
  )
)
